# CAPSTONE_PCB_TAKE1.net
KiCad netlist of a schematic drawn in EAGLE
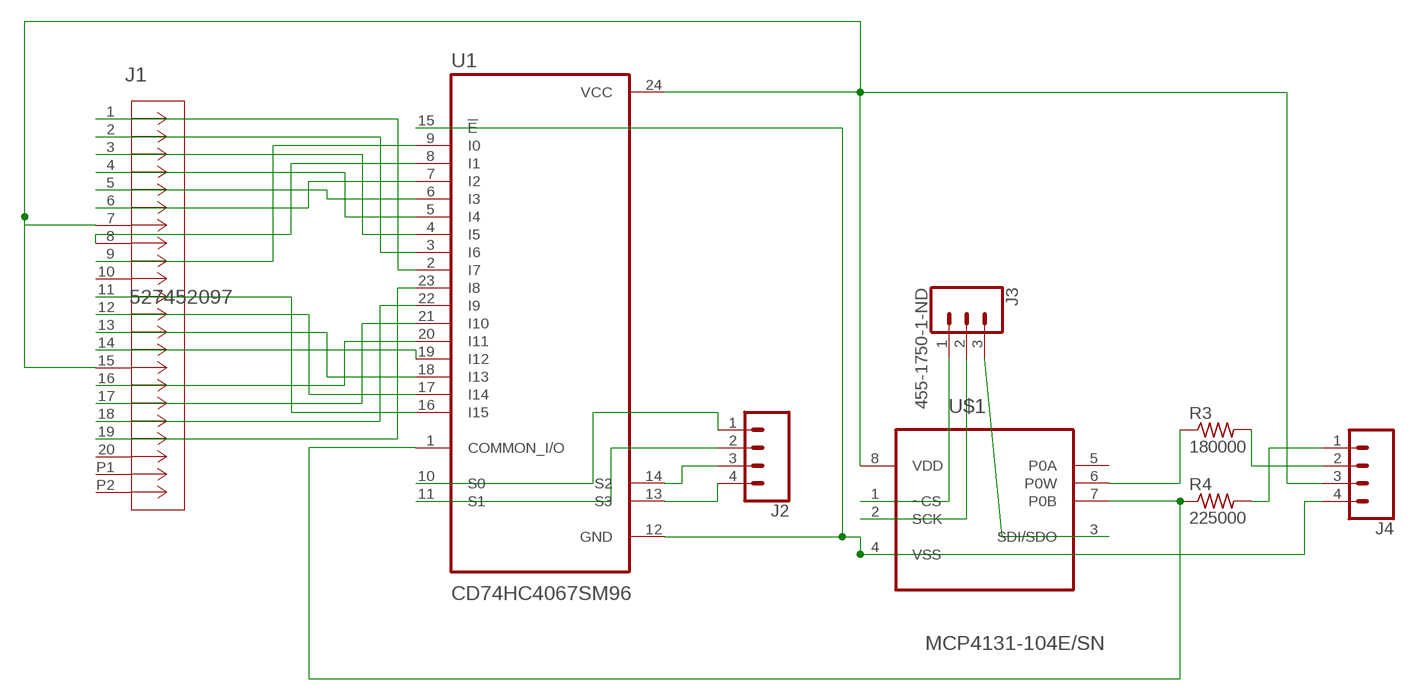
[diagram p0: schematic, sheet 1]

(export (version "E")
  (design (tool "Eeschema 10.0.6"))
  (components
    (comp (ref "J1")
      (value "527452097")
      (footprint "eagle-import:CON_527452097_MOL")
      (fields (field (name "MF") "Molex"))
      (libsource (lib "eagle-import") (part "527452097"))
    )
    (comp (ref "J2")
      (value "CONN_04LOCK")
      (footprint "eagle-import:1X04_LOCK")
      (libsource (lib "eagle-import") (part "CONN_04LOCK"))
    )
    (comp (ref "J3")
      (value "455-1750-1-ND")
      (footprint "eagle-import:1X03")
      (libsource (lib "eagle-import") (part "CONN_03"))
    )
    (comp (ref "J4")
      (value "CONN_04LOCK")
      (footprint "eagle-import:1X04_LOCK")
      (libsource (lib "eagle-import") (part "CONN_04LOCK"))
    )
    (comp (ref "R3")
      (value "180000")
      (footprint "eagle-import:0204V")
      (libsource (lib "eagle-import") (part "R-US_0204/2V"))
    )
    (comp (ref "R4")
      (value "225000")
      (footprint "eagle-import:0204V")
      (libsource (lib "eagle-import") (part "R-US_0204/2V"))
    )
    (comp (ref "U$1")
      (value "MCP4131-104E/SN")
      (footprint "eagle-import:SOIC127P600X175-8N")
      (fields (field (name "DIGIKEY_PART_NUMBER") "MCP4131-104E/SN-ND") (field (name "MF") "Microchip"))
      (libsource (lib "eagle-import") (part "MCP4131-104E/SN"))
    )
    (comp (ref "U1")
      (value "CD74HC4067SM96")
      (footprint "eagle-import:SOP65P780X200-24N")
      (fields (field (name "DIGIKEY_PART_NUMBER") "296-9226-1-ND") (field (name "MF") "Texas Instruments"))
      (libsource (lib "eagle-import") (part "CD74HC4067SM96"))
    )
  )
  (nets
    (net (code "1") (name "Net-(J4-Pad1)") (class "Default")
      (node (ref "J4") (pin "1") (pinfunction "1_1") (pintype "passive"))
      (node (ref "R4") (pin "2") (pinfunction "2_2") (pintype "passive"))
    )
    (net (code "2") (name "Net-(J4-Pad2)") (class "Default")
      (node (ref "J4") (pin "2") (pinfunction "2_2") (pintype "passive"))
      (node (ref "R3") (pin "2") (pinfunction "2_2") (pintype "passive"))
    )
    (net (code "3") (name "Net-(U$1-P0B)") (class "Default")
      (node (ref "R4") (pin "1") (pinfunction "1_1") (pintype "passive"))
      (node (ref "U$1") (pin "7") (pinfunction "P0B_7") (pintype "passive"))
      (node (ref "U1") (pin "1") (pinfunction "COMMON_I/O_1") (pintype "bidirectional"))
    )
    (net (code "4") (name "Net-(U$1-P0W)") (class "Default")
      (node (ref "R3") (pin "1") (pinfunction "1_1") (pintype "passive"))
      (node (ref "U$1") (pin "6") (pinfunction "P0W_6") (pintype "passive"))
    )
    (net (code "5") (name "Net-(U$1-SCK)") (class "Default")
      (node (ref "J3") (pin "2") (pinfunction "2_2") (pintype "passive"))
      (node (ref "U$1") (pin "2") (pinfunction "SCK_2") (pintype "input"))
    )
    (net (code "6") (name "Net-(U$1-SDI{slash}SDO)") (class "Default")
      (node (ref "J3") (pin "3") (pinfunction "3_3") (pintype "passive"))
      (node (ref "U$1") (pin "3") (pinfunction "SDI/SDO_3") (pintype "bidirectional"))
    )
    (net (code "7") (name "Net-(U$1-VDD)") (class "Default")
      (node (ref "J1") (pin "15") (pinfunction "15_15") (pintype "passive"))
      (node (ref "J1") (pin "7") (pinfunction "7_7") (pintype "passive"))
      (node (ref "J4") (pin "3") (pinfunction "3_3") (pintype "passive"))
      (node (ref "U$1") (pin "8") (pinfunction "VDD_8") (pintype "power_in"))
      (node (ref "U1") (pin "24") (pinfunction "VCC_24") (pintype "power_in"))
    )
    (net (code "8") (name "Net-(U$1-VSS)") (class "Default")
      (node (ref "J4") (pin "4") (pinfunction "4_4") (pintype "passive"))
      (node (ref "U$1") (pin "4") (pinfunction "VSS_4") (pintype "power_in"))
      (node (ref "U1") (pin "12") (pinfunction "GND_12") (pintype "power_in"))
      (node (ref "U1") (pin "15") (pinfunction "~{E}_15") (pintype "input"))
    )
    (net (code "9") (name "Net-(U$1-~{CS})") (class "Default")
      (node (ref "J3") (pin "1") (pinfunction "1_1") (pintype "passive"))
      (node (ref "U$1") (pin "1") (pinfunction "~{CS}_1") (pintype "input"))
    )
    (net (code "10") (name "Net-(U1-I0)") (class "Default")
      (node (ref "J1") (pin "9") (pinfunction "9_9") (pintype "passive"))
      (node (ref "U1") (pin "9") (pinfunction "I0_9") (pintype "input"))
    )
    (net (code "11") (name "Net-(U1-I1)") (class "Default")
      (node (ref "J1") (pin "8") (pinfunction "8_8") (pintype "passive"))
      (node (ref "U1") (pin "8") (pinfunction "I1_8") (pintype "input"))
    )
    (net (code "12") (name "Net-(U1-I2)") (class "Default")
      (node (ref "J1") (pin "6") (pinfunction "6_6") (pintype "passive"))
      (node (ref "U1") (pin "7") (pinfunction "I2_7") (pintype "input"))
    )
    (net (code "13") (name "Net-(U1-I3)") (class "Default")
      (node (ref "J1") (pin "5") (pinfunction "5_5") (pintype "passive"))
      (node (ref "U1") (pin "6") (pinfunction "I3_6") (pintype "input"))
    )
    (net (code "14") (name "Net-(U1-I4)") (class "Default")
      (node (ref "J1") (pin "4") (pinfunction "4_4") (pintype "passive"))
      (node (ref "U1") (pin "5") (pinfunction "I4_5") (pintype "input"))
    )
    (net (code "15") (name "Net-(U1-I5)") (class "Default")
      (node (ref "J1") (pin "3") (pinfunction "3_3") (pintype "passive"))
      (node (ref "U1") (pin "4") (pinfunction "I5_4") (pintype "input"))
    )
    (net (code "16") (name "Net-(U1-I6)") (class "Default")
      (node (ref "J1") (pin "2") (pinfunction "2_2") (pintype "passive"))
      (node (ref "U1") (pin "3") (pinfunction "I6_3") (pintype "input"))
    )
    (net (code "17") (name "Net-(U1-I7)") (class "Default")
      (node (ref "J1") (pin "1") (pinfunction "1_1") (pintype "passive"))
      (node (ref "U1") (pin "2") (pinfunction "I7_2") (pintype "input"))
    )
    (net (code "18") (name "Net-(U1-I8)") (class "Default")
      (node (ref "J1") (pin "19") (pinfunction "19_19") (pintype "passive"))
      (node (ref "U1") (pin "23") (pinfunction "I8_23") (pintype "input"))
    )
    (net (code "19") (name "Net-(U1-I9)") (class "Default")
      (node (ref "J1") (pin "18") (pinfunction "18_18") (pintype "passive"))
      (node (ref "U1") (pin "22") (pinfunction "I9_22") (pintype "input"))
    )
    (net (code "20") (name "Net-(U1-I10)") (class "Default")
      (node (ref "J1") (pin "17") (pinfunction "17_17") (pintype "passive"))
      (node (ref "U1") (pin "21") (pinfunction "I10_21") (pintype "input"))
    )
    (net (code "21") (name "Net-(U1-I11)") (class "Default")
      (node (ref "J1") (pin "16") (pinfunction "16_16") (pintype "passive"))
      (node (ref "U1") (pin "20") (pinfunction "I11_20") (pintype "input"))
    )
    (net (code "22") (name "Net-(U1-I12)") (class "Default")
      (node (ref "J1") (pin "14") (pinfunction "14_14") (pintype "passive"))
      (node (ref "U1") (pin "19") (pinfunction "I12_19") (pintype "input"))
    )
    (net (code "23") (name "Net-(U1-I13)") (class "Default")
      (node (ref "J1") (pin "13") (pinfunction "13_13") (pintype "passive"))
      (node (ref "U1") (pin "18") (pinfunction "I13_18") (pintype "input"))
    )
    (net (code "24") (name "Net-(U1-I14)") (class "Default")
      (node (ref "J1") (pin "12") (pinfunction "12_12") (pintype "passive"))
      (node (ref "U1") (pin "17") (pinfunction "I14_17") (pintype "input"))
    )
    (net (code "25") (name "Net-(U1-I15)") (class "Default")
      (node (ref "J1") (pin "11") (pinfunction "11_11") (pintype "passive"))
      (node (ref "U1") (pin "16") (pinfunction "I15_16") (pintype "input"))
    )
    (net (code "26") (name "Net-(U1-S0)") (class "Default")
      (node (ref "J2") (pin "1") (pinfunction "1_1") (pintype "passive"))
      (node (ref "U1") (pin "10") (pinfunction "S0_10") (pintype "bidirectional"))
    )
    (net (code "27") (name "Net-(U1-S1)") (class "Default")
      (node (ref "J2") (pin "2") (pinfunction "2_2") (pintype "passive"))
      (node (ref "U1") (pin "11") (pinfunction "S1_11") (pintype "bidirectional"))
    )
    (net (code "28") (name "Net-(U1-S2)") (class "Default")
      (node (ref "J2") (pin "3") (pinfunction "3_3") (pintype "passive"))
      (node (ref "U1") (pin "14") (pinfunction "S2_14") (pintype "bidirectional"))
    )
    (net (code "29") (name "Net-(U1-S3)") (class "Default")
      (node (ref "J2") (pin "4") (pinfunction "4_4") (pintype "passive"))
      (node (ref "U1") (pin "13") (pinfunction "S3_13") (pintype "bidirectional"))
    )
    (net (code "30") (name "unconnected-(J1-Pad10)") (class "Default")
      (node (ref "J1") (pin "10") (pinfunction "10_10") (pintype "passive"))
    )
    (net (code "31") (name "unconnected-(J1-Pad20)") (class "Default")
      (node (ref "J1") (pin "20") (pinfunction "20_20") (pintype "passive"))
    )
    (net (code "32") (name "unconnected-(J1-PadP1)") (class "Default")
      (node (ref "J1") (pin "P1") (pinfunction "P1_P1") (pintype "passive"))
    )
    (net (code "33") (name "unconnected-(J1-PadP2)") (class "Default")
      (node (ref "J1") (pin "P2") (pinfunction "P2_P2") (pintype "passive"))
    )
    (net (code "34") (name "unconnected-(U$1-P0A-Pad5)") (class "Default")
      (node (ref "U$1") (pin "5") (pinfunction "P0A_5") (pintype "passive"))
    )
  )
)
